# Stress_Wheat_bridge_board.net
KiCad netlist of a schematic drawn in EAGLE
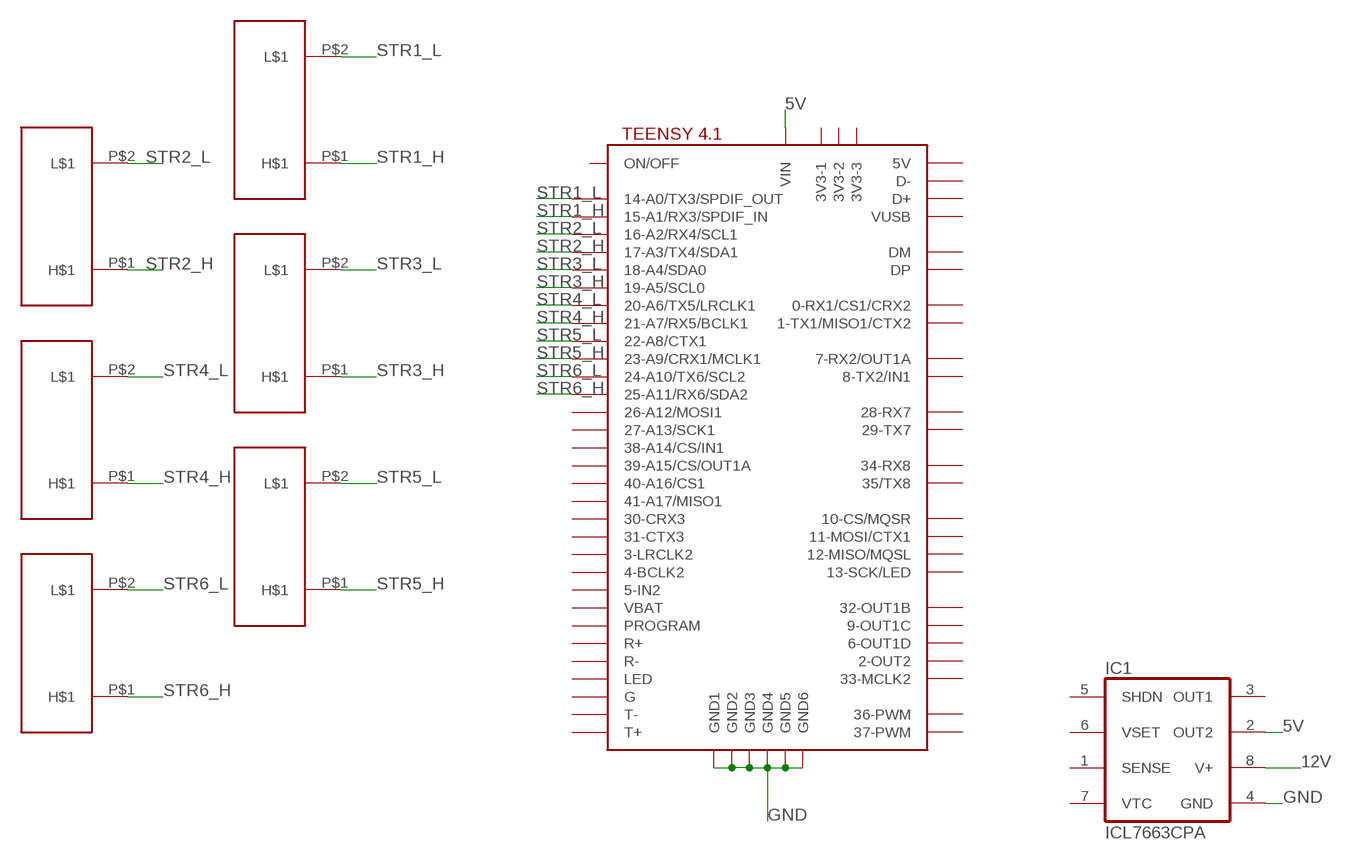
[diagram p0: schematic, sheet 1]

(export (version "E")
  (design (tool "Eeschema 10.0.6"))
  (components
    (comp (ref "IC1")
      (value "ICL7663CPA")
      (footprint "eagle-import:DIL08")
      (libsource (lib "eagle-import") (part "ICL7663CPA"))
    )
    (comp (ref "U$1")
      (value "STR_GAUGE")
      (footprint "eagle-import:STR_GAUGE")
      (libsource (lib "eagle-import") (part "STR_GAUGE"))
    )
    (comp (ref "U$2")
      (value "STR_GAUGE")
      (footprint "eagle-import:STR_GAUGE")
      (libsource (lib "eagle-import") (part "STR_GAUGE"))
    )
    (comp (ref "U$3")
      (value "TEENSY41")
      (footprint "eagle-import:TEENSY41")
      (libsource (lib "eagle-import") (part "TEENSY41"))
    )
    (comp (ref "U$4")
      (value "STR_GAUGE")
      (footprint "eagle-import:STR_GAUGE")
      (libsource (lib "eagle-import") (part "STR_GAUGE"))
    )
    (comp (ref "U$5")
      (value "STR_GAUGE")
      (footprint "eagle-import:STR_GAUGE")
      (libsource (lib "eagle-import") (part "STR_GAUGE"))
    )
    (comp (ref "U$6")
      (value "STR_GAUGE")
      (footprint "eagle-import:STR_GAUGE")
      (libsource (lib "eagle-import") (part "STR_GAUGE"))
    )
    (comp (ref "U$7")
      (value "STR_GAUGE")
      (footprint "eagle-import:STR_GAUGE")
      (libsource (lib "eagle-import") (part "STR_GAUGE"))
    )
  )
  (nets
    (net (code "1") (name "/5V") (class "Default")
      (node (ref "IC1") (pin "2") (pinfunction "OUT2_2") (pintype "output"))
      (node (ref "U$3") (pin "VIN") (pinfunction "VIN_VIN") (pintype "bidirectional"))
    )
    (net (code "2") (name "/12V") (class "Default")
      (node (ref "IC1") (pin "8") (pinfunction "V+_8") (pintype "power_in"))
    )
    (net (code "3") (name "/GND") (class "Default")
      (node (ref "IC1") (pin "4") (pinfunction "GND_4") (pintype "power_in"))
      (node (ref "U$3") (pin "GND1") (pinfunction "GND1_GND1") (pintype "bidirectional"))
      (node (ref "U$3") (pin "GND2") (pinfunction "GND2_GND2") (pintype "bidirectional"))
      (node (ref "U$3") (pin "GND3") (pinfunction "GND3_GND3") (pintype "bidirectional"))
      (node (ref "U$3") (pin "GND4") (pinfunction "GND4_GND4") (pintype "bidirectional"))
      (node (ref "U$3") (pin "GND5") (pinfunction "GND5_GND5") (pintype "bidirectional"))
      (node (ref "U$3") (pin "GND6") (pinfunction "GND6_GND6") (pintype "bidirectional"))
    )
    (net (code "4") (name "/STR1_H") (class "Default")
      (node (ref "U$1") (pin "P$1") (pinfunction "H$1_P$1") (pintype "bidirectional"))
      (node (ref "U$3") (pin "15-A1/RX3/SPDIF_IN") (pinfunction "15-A1/RX3/SPDIF_IN_15-A1/RX3/SPDIF_IN") (pintype "bidirectional"))
    )
    (net (code "5") (name "/STR1_L") (class "Default")
      (node (ref "U$1") (pin "P$2") (pinfunction "L$1_P$2") (pintype "bidirectional"))
      (node (ref "U$3") (pin "14-A0/TX3/SPDIF_OUT") (pinfunction "14-A0/TX3/SPDIF_OUT_14-A0/TX3/SPDIF_OUT") (pintype "bidirectional"))
    )
    (net (code "6") (name "/STR2_H") (class "Default")
      (node (ref "U$2") (pin "P$1") (pinfunction "H$1_P$1") (pintype "bidirectional"))
      (node (ref "U$3") (pin "17-A3/TX4/SDA1") (pinfunction "17-A3/TX4/SDA1_17-A3/TX4/SDA1") (pintype "bidirectional"))
    )
    (net (code "7") (name "/STR2_L") (class "Default")
      (node (ref "U$2") (pin "P$2") (pinfunction "L$1_P$2") (pintype "bidirectional"))
      (node (ref "U$3") (pin "16-A2/RX4/SCL1") (pinfunction "16-A2/RX4/SCL1_16-A2/RX4/SCL1") (pintype "bidirectional"))
    )
    (net (code "8") (name "/STR3_H") (class "Default")
      (node (ref "U$3") (pin "19-A5/SCL0") (pinfunction "19-A5/SCL0_19-A5/SCL0") (pintype "bidirectional"))
      (node (ref "U$4") (pin "P$1") (pinfunction "H$1_P$1") (pintype "bidirectional"))
    )
    (net (code "9") (name "/STR3_L") (class "Default")
      (node (ref "U$3") (pin "18-A4/SDA0") (pinfunction "18-A4/SDA0_18-A4/SDA0") (pintype "bidirectional"))
      (node (ref "U$4") (pin "P$2") (pinfunction "L$1_P$2") (pintype "bidirectional"))
    )
    (net (code "10") (name "/STR4_H") (class "Default")
      (node (ref "U$3") (pin "21-A7/RX5/BCLK1") (pinfunction "21-A7/RX5/BCLK1_21-A7/RX5/BCLK1") (pintype "bidirectional"))
      (node (ref "U$5") (pin "P$1") (pinfunction "H$1_P$1") (pintype "bidirectional"))
    )
    (net (code "11") (name "/STR4_L") (class "Default")
      (node (ref "U$3") (pin "20-A6/TX5/LRCLK1") (pinfunction "20-A6/TX5/LRCLK1_20-A6/TX5/LRCLK1") (pintype "bidirectional"))
      (node (ref "U$5") (pin "P$2") (pinfunction "L$1_P$2") (pintype "bidirectional"))
    )
    (net (code "12") (name "/STR5_H") (class "Default")
      (node (ref "U$3") (pin "23-A9/CRX1/MCLK1") (pinfunction "23-A9/CRX1/MCLK1_23-A9/CRX1/MCLK1") (pintype "bidirectional"))
      (node (ref "U$6") (pin "P$1") (pinfunction "H$1_P$1") (pintype "bidirectional"))
    )
    (net (code "13") (name "/STR5_L") (class "Default")
      (node (ref "U$3") (pin "22-A8/CTX1") (pinfunction "22-A8/CTX1_22-A8/CTX1") (pintype "bidirectional"))
      (node (ref "U$6") (pin "P$2") (pinfunction "L$1_P$2") (pintype "bidirectional"))
    )
    (net (code "14") (name "/STR6_H") (class "Default")
      (node (ref "U$3") (pin "25-A11/RX6/SDA2") (pinfunction "25-A11/RX6/SDA2_25-A11/RX6/SDA2") (pintype "bidirectional"))
      (node (ref "U$7") (pin "P$1") (pinfunction "H$1_P$1") (pintype "bidirectional"))
    )
    (net (code "15") (name "/STR6_L") (class "Default")
      (node (ref "U$3") (pin "24-A10/TX6/SCL2") (pinfunction "24-A10/TX6/SCL2_24-A10/TX6/SCL2") (pintype "bidirectional"))
      (node (ref "U$7") (pin "P$2") (pinfunction "L$1_P$2") (pintype "bidirectional"))
    )
    (net (code "16") (name "unconnected-(IC1-OUT1-Pad3)") (class "Default")
      (node (ref "IC1") (pin "3") (pinfunction "OUT1_3") (pintype "output"))
    )
    (net (code "17") (name "unconnected-(IC1-SENSE-Pad1)") (class "Default")
      (node (ref "IC1") (pin "1") (pinfunction "SENSE_1") (pintype "input"))
    )
    (net (code "18") (name "unconnected-(IC1-SHDN-Pad5)") (class "Default")
      (node (ref "IC1") (pin "5") (pinfunction "SHDN_5") (pintype "input"))
    )
    (net (code "19") (name "unconnected-(IC1-VSET-Pad6)") (class "Default")
      (node (ref "IC1") (pin "6") (pinfunction "VSET_6") (pintype "input"))
    )
    (net (code "20") (name "unconnected-(IC1-VTC-Pad7)") (class "Default")
      (node (ref "IC1") (pin "7") (pinfunction "VTC_7") (pintype "passive"))
    )
    (net (code "21") (name "unconnected-(U$3-5V-Pad+5V)") (class "Default")
      (node (ref "U$3") (pin "+5V") (pinfunction "5V_+5V") (pintype "bidirectional"))
    )
    (net (code "22") (name "unconnected-(U$3-8-TX2{slash}IN1-Pad8-TX2{slash}IN2)") (class "Default")
      (node (ref "U$3") (pin "8-TX2/IN2") (pinfunction "8-TX2/IN1_8-TX2/IN2") (pintype "bidirectional"))
    )
    (net (code "23") (name "unconnected-(U$3-10-CS{slash}MQSR-Pad10-CS\\MQSR)") (class "Default")
      (node (ref "U$3") (pin "10-CS\\MQSR") (pinfunction "10-CS/MQSR_10-CS\\MQSR") (pintype "bidirectional"))
    )
    (net (code "24") (name "unconnected-(U$3-35{slash}TX8-Pad35-TX8)") (class "Default")
      (node (ref "U$3") (pin "35-TX8") (pinfunction "35/TX8_35-TX8") (pintype "bidirectional"))
    )
    (net (code "25") (name "unconnected-(U$3-Pad0-RX1{slash}CS1{slash}CRX2)") (class "Default")
      (node (ref "U$3") (pin "0-RX1/CS1/CRX2") (pinfunction "0-RX1/CS1/CRX2_0-RX1/CS1/CRX2") (pintype "bidirectional"))
    )
    (net (code "26") (name "unconnected-(U$3-Pad1-TX1{slash}MISO1{slash}CTX2)") (class "Default")
      (node (ref "U$3") (pin "1-TX1/MISO1/CTX2") (pinfunction "1-TX1/MISO1/CTX2_1-TX1/MISO1/CTX2") (pintype "bidirectional"))
    )
    (net (code "27") (name "unconnected-(U$3-Pad2-OUT2)") (class "Default")
      (node (ref "U$3") (pin "2-OUT2") (pinfunction "2-OUT2_2-OUT2") (pintype "bidirectional"))
    )
    (net (code "28") (name "unconnected-(U$3-Pad3-LRCLK2)") (class "Default")
      (node (ref "U$3") (pin "3-LRCLK2") (pinfunction "3-LRCLK2_3-LRCLK2") (pintype "bidirectional"))
    )
    (net (code "29") (name "unconnected-(U$3-Pad3V3-1)") (class "Default")
      (node (ref "U$3") (pin "3V3-1") (pinfunction "3V3-1_3V3-1") (pintype "bidirectional"))
    )
    (net (code "30") (name "unconnected-(U$3-Pad3V3-2)") (class "Default")
      (node (ref "U$3") (pin "3V3-2") (pinfunction "3V3-2_3V3-2") (pintype "bidirectional"))
    )
    (net (code "31") (name "unconnected-(U$3-Pad3V3-3)") (class "Default")
      (node (ref "U$3") (pin "3V3-3") (pinfunction "3V3-3_3V3-3") (pintype "bidirectional"))
    )
    (net (code "32") (name "unconnected-(U$3-Pad4-BCLK2)") (class "Default")
      (node (ref "U$3") (pin "4-BCLK2") (pinfunction "4-BCLK2_4-BCLK2") (pintype "bidirectional"))
    )
    (net (code "33") (name "unconnected-(U$3-Pad5-IN2)") (class "Default")
      (node (ref "U$3") (pin "5-IN2") (pinfunction "5-IN2_5-IN2") (pintype "bidirectional"))
    )
    (net (code "34") (name "unconnected-(U$3-Pad6-OUT1D)") (class "Default")
      (node (ref "U$3") (pin "6-OUT1D") (pinfunction "6-OUT1D_6-OUT1D") (pintype "bidirectional"))
    )
    (net (code "35") (name "unconnected-(U$3-Pad7-RX2{slash}OUT1A)") (class "Default")
      (node (ref "U$3") (pin "7-RX2/OUT1A") (pinfunction "7-RX2/OUT1A_7-RX2/OUT1A") (pintype "bidirectional"))
    )
    (net (code "36") (name "unconnected-(U$3-Pad9-OUT1C)") (class "Default")
      (node (ref "U$3") (pin "9-OUT1C") (pinfunction "9-OUT1C_9-OUT1C") (pintype "bidirectional"))
    )
    (net (code "37") (name "unconnected-(U$3-Pad11-MOSI{slash}CTX1)") (class "Default")
      (node (ref "U$3") (pin "11-MOSI/CTX1") (pinfunction "11-MOSI/CTX1_11-MOSI/CTX1") (pintype "bidirectional"))
    )
    (net (code "38") (name "unconnected-(U$3-Pad12-MISO{slash}MQSL)") (class "Default")
      (node (ref "U$3") (pin "12-MISO/MQSL") (pinfunction "12-MISO/MQSL_12-MISO/MQSL") (pintype "bidirectional"))
    )
    (net (code "39") (name "unconnected-(U$3-Pad13-SCK{slash}LED)") (class "Default")
      (node (ref "U$3") (pin "13-SCK/LED") (pinfunction "13-SCK/LED_13-SCK/LED") (pintype "bidirectional"))
    )
    (net (code "40") (name "unconnected-(U$3-Pad26-A12{slash}MOSI1)") (class "Default")
      (node (ref "U$3") (pin "26-A12/MOSI1") (pinfunction "26-A12/MOSI1_26-A12/MOSI1") (pintype "bidirectional"))
    )
    (net (code "41") (name "unconnected-(U$3-Pad27-A13{slash}SCK1)") (class "Default")
      (node (ref "U$3") (pin "27-A13/SCK1") (pinfunction "27-A13/SCK1_27-A13/SCK1") (pintype "bidirectional"))
    )
    (net (code "42") (name "unconnected-(U$3-Pad28-RX7)") (class "Default")
      (node (ref "U$3") (pin "28-RX7") (pinfunction "28-RX7_28-RX7") (pintype "bidirectional"))
    )
    (net (code "43") (name "unconnected-(U$3-Pad29-TX7)") (class "Default")
      (node (ref "U$3") (pin "29-TX7") (pinfunction "29-TX7_29-TX7") (pintype "bidirectional"))
    )
    (net (code "44") (name "unconnected-(U$3-Pad30-CRX3)") (class "Default")
      (node (ref "U$3") (pin "30-CRX3") (pinfunction "30-CRX3_30-CRX3") (pintype "bidirectional"))
    )
    (net (code "45") (name "unconnected-(U$3-Pad31-CTX3)") (class "Default")
      (node (ref "U$3") (pin "31-CTX3") (pinfunction "31-CTX3_31-CTX3") (pintype "bidirectional"))
    )
    (net (code "46") (name "unconnected-(U$3-Pad32-OUT1B)") (class "Default")
      (node (ref "U$3") (pin "32-OUT1B") (pinfunction "32-OUT1B_32-OUT1B") (pintype "bidirectional"))
    )
    (net (code "47") (name "unconnected-(U$3-Pad33-MCLK2)") (class "Default")
      (node (ref "U$3") (pin "33-MCLK2") (pinfunction "33-MCLK2_33-MCLK2") (pintype "bidirectional"))
    )
    (net (code "48") (name "unconnected-(U$3-Pad34-RX8)") (class "Default")
      (node (ref "U$3") (pin "34-RX8") (pinfunction "34-RX8_34-RX8") (pintype "bidirectional"))
    )
    (net (code "49") (name "unconnected-(U$3-Pad36-PWM)") (class "Default")
      (node (ref "U$3") (pin "36-PWM") (pinfunction "36-PWM_36-PWM") (pintype "bidirectional"))
    )
    (net (code "50") (name "unconnected-(U$3-Pad37-PWM)") (class "Default")
      (node (ref "U$3") (pin "37-PWM") (pinfunction "37-PWM_37-PWM") (pintype "bidirectional"))
    )
    (net (code "51") (name "unconnected-(U$3-Pad38-A14{slash}CS{slash}IN1)") (class "Default")
      (node (ref "U$3") (pin "38-A14/CS/IN1") (pinfunction "38-A14/CS/IN1_38-A14/CS/IN1") (pintype "bidirectional"))
    )
    (net (code "52") (name "unconnected-(U$3-Pad39-A15{slash}CS{slash}OUT1A)") (class "Default")
      (node (ref "U$3") (pin "39-A15/CS/OUT1A") (pinfunction "39-A15/CS/OUT1A_39-A15/CS/OUT1A") (pintype "bidirectional"))
    )
    (net (code "53") (name "unconnected-(U$3-Pad40-A16{slash}CS1)") (class "Default")
      (node (ref "U$3") (pin "40-A16/CS1") (pinfunction "40-A16/CS1_40-A16/CS1") (pintype "bidirectional"))
    )
    (net (code "54") (name "unconnected-(U$3-Pad41-A17{slash}MISO1)") (class "Default")
      (node (ref "U$3") (pin "41-A17/MISO1") (pinfunction "41-A17/MISO1_41-A17/MISO1") (pintype "bidirectional"))
    )
    (net (code "55") (name "unconnected-(U$3-PadD+)") (class "Default")
      (node (ref "U$3") (pin "D+") (pinfunction "D+_D+") (pintype "bidirectional"))
    )
    (net (code "56") (name "unconnected-(U$3-PadD-)") (class "Default")
      (node (ref "U$3") (pin "D-") (pinfunction "D-_D-") (pintype "bidirectional"))
    )
    (net (code "57") (name "unconnected-(U$3-PadDM)") (class "Default")
      (node (ref "U$3") (pin "DM") (pinfunction "DM_DM") (pintype "bidirectional"))
    )
    (net (code "58") (name "unconnected-(U$3-PadDP)") (class "Default")
      (node (ref "U$3") (pin "DP") (pinfunction "DP_DP") (pintype "bidirectional"))
    )
    (net (code "59") (name "unconnected-(U$3-PadG)") (class "Default")
      (node (ref "U$3") (pin "G") (pinfunction "G_G") (pintype "bidirectional"))
    )
    (net (code "60") (name "unconnected-(U$3-PadLED)") (class "Default")
      (node (ref "U$3") (pin "LED") (pinfunction "LED_LED") (pintype "bidirectional"))
    )
    (net (code "61") (name "unconnected-(U$3-PadON{slash}OFF)") (class "Default")
      (node (ref "U$3") (pin "ON/OFF") (pinfunction "ON/OFF_ON/OFF") (pintype "bidirectional"))
    )
    (net (code "62") (name "unconnected-(U$3-PadPROGRAM)") (class "Default")
      (node (ref "U$3") (pin "PROGRAM") (pinfunction "PROGRAM_PROGRAM") (pintype "bidirectional"))
    )
    (net (code "63") (name "unconnected-(U$3-PadR+)") (class "Default")
      (node (ref "U$3") (pin "R+") (pinfunction "R+_R+") (pintype "bidirectional"))
    )
    (net (code "64") (name "unconnected-(U$3-PadR-)") (class "Default")
      (node (ref "U$3") (pin "R-") (pinfunction "R-_R-") (pintype "bidirectional"))
    )
    (net (code "65") (name "unconnected-(U$3-PadT+)") (class "Default")
      (node (ref "U$3") (pin "T+") (pinfunction "T+_T+") (pintype "bidirectional"))
    )
    (net (code "66") (name "unconnected-(U$3-PadT-)") (class "Default")
      (node (ref "U$3") (pin "T-") (pinfunction "T-_T-") (pintype "bidirectional"))
    )
    (net (code "67") (name "unconnected-(U$3-PadVBAT)") (class "Default")
      (node (ref "U$3") (pin "VBAT") (pinfunction "VBAT_VBAT") (pintype "bidirectional"))
    )
    (net (code "68") (name "unconnected-(U$3-PadVUSB)") (class "Default")
      (node (ref "U$3") (pin "VUSB") (pinfunction "VUSB_VUSB") (pintype "bidirectional"))
    )
  )
)
